# POWER.net
KiCad netlist of a schematic drawn in Altium Designer
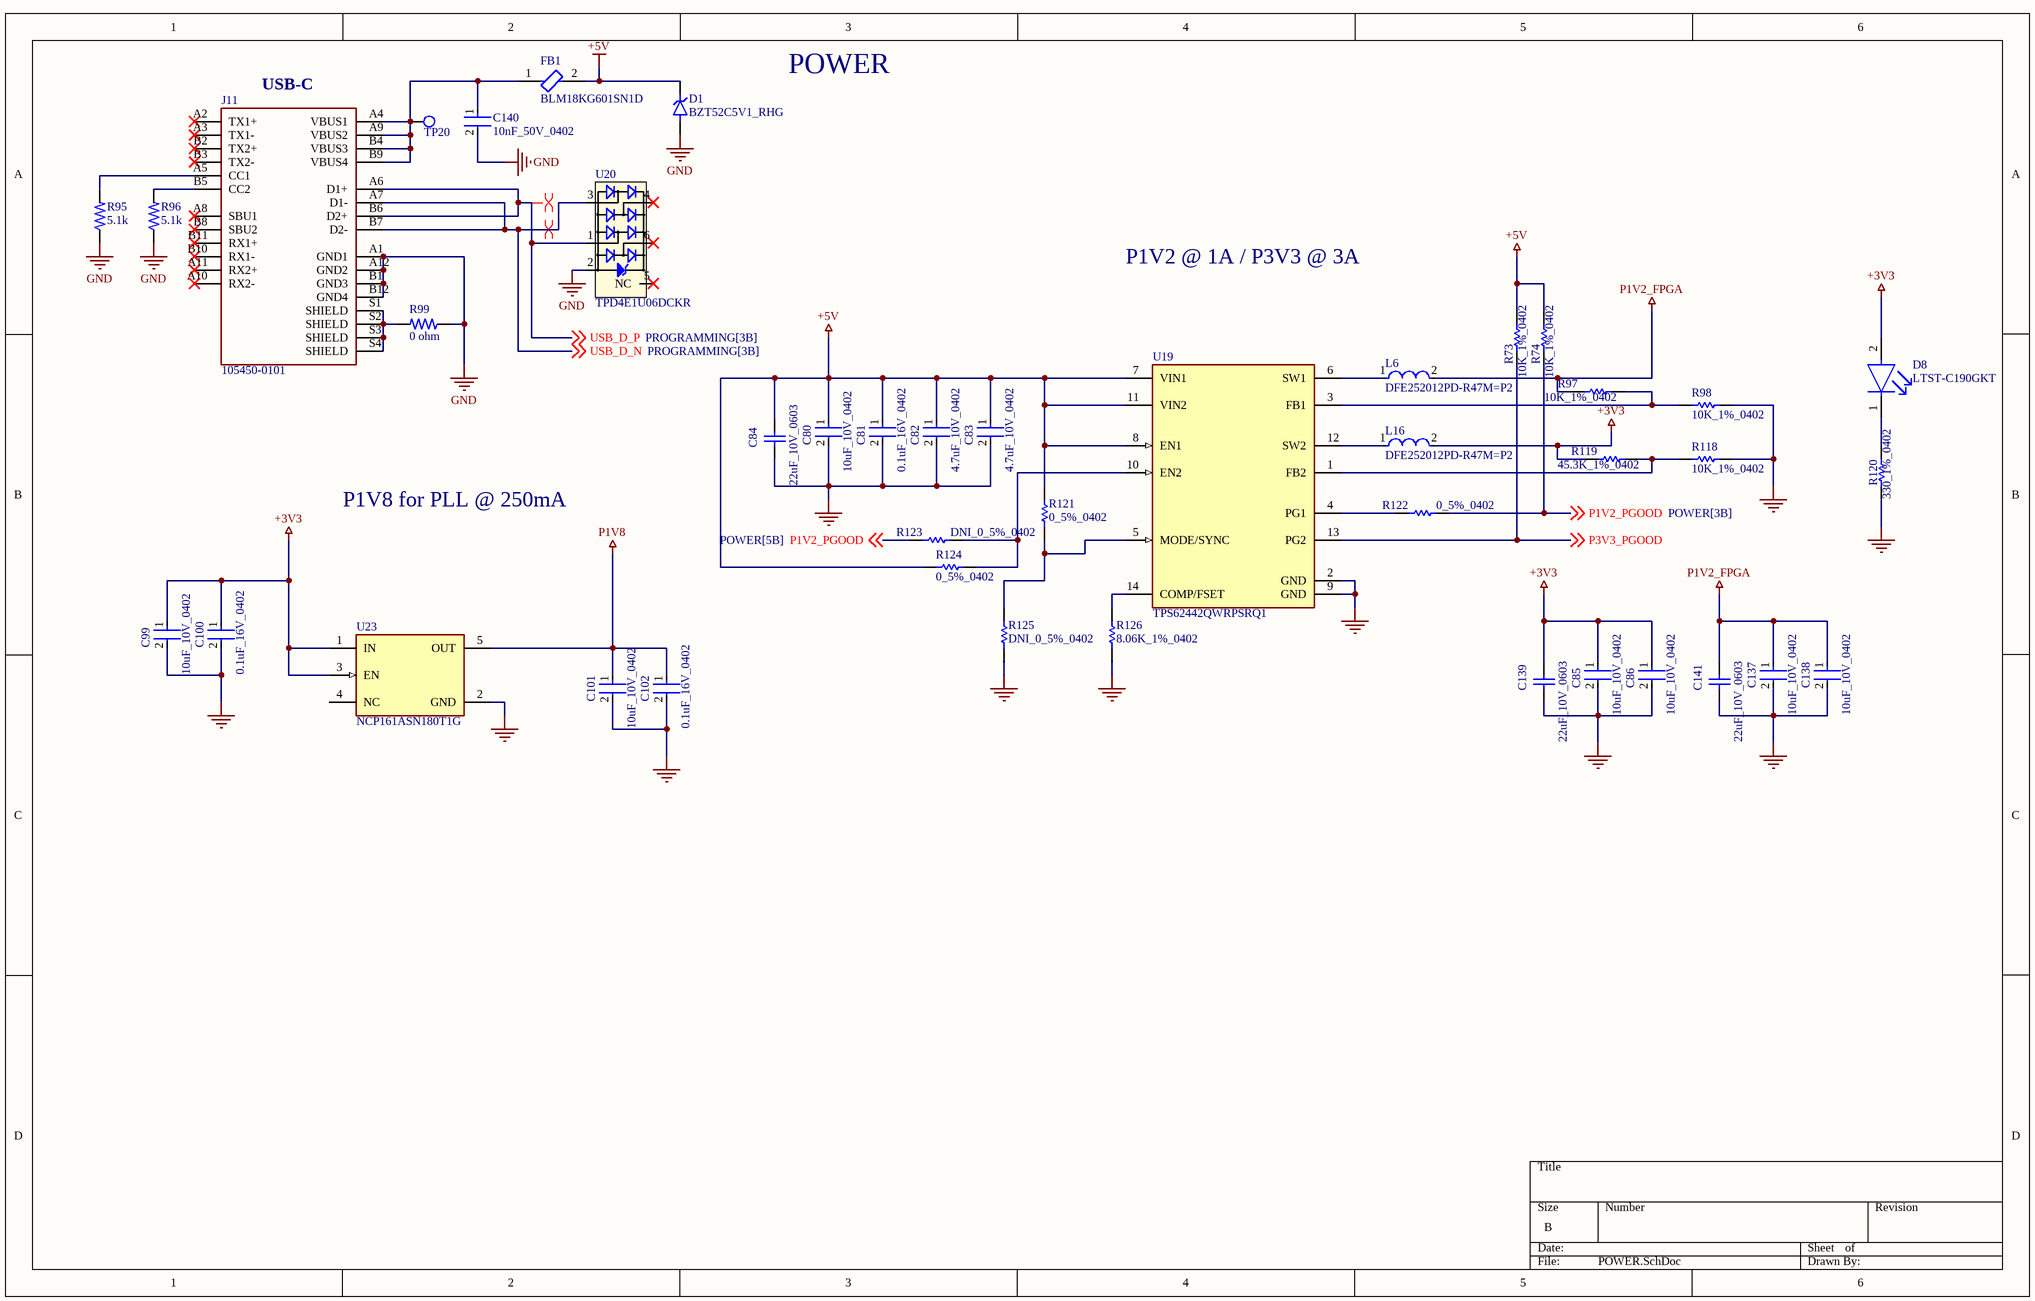
[diagram p0: POWER.SchDoc]

(export (version "E")
  (design (tool "Eeschema 10.0.6"))
  (components
    (comp (ref "C80")
      (value "10uF_10V_0402")
      (footprint "FP-CL05A106MP5NUNC-MFG")
      (description "CAP CER 10UF 10V X5R 0402")
      (fields
        (field (name "OCTOPART") "https://octopart.com/cl05a106mp5nunc-samsung-22457395")
        (field (name "TOLERANCE") "20%")
      )
      (libsource (lib "Altium Content Vault") (part "b4654b650e69147ec39a6b967a45e02"))
    )
    (comp (ref "C81")
      (value "0.1uF_16V_0402")
      (footprint "FP-C0402-BB-MFG")
      (description "CAP CER 0.1UF 16V 5% X7R 0402")
      (fields
        (field (name "MANUFACTURER") "Kemet")
        (field (name "MANUFACTURER PART NUMBER") "C0402C104J4RACTU")
      )
      (libsource (lib "Altium Content Vault") (part "b4654b650e69147ec39a6b967a45e02"))
    )
    (comp (ref "C82")
      (value "4.7uF_10V_0402")
      (footprint "FP-C1005-050-0_15-MFG")
      (description "CAP CER 4.7UF 10V X5R 0402")
      (fields (field (name "TOLERANCE") "10%"))
      (libsource (lib "Altium Content Vault") (part "b4654b650e69147ec39a6b967a45e02"))
    )
    (comp (ref "C83")
      (value "4.7uF_10V_0402")
      (footprint "FP-C1005-050-0_15-MFG")
      (description "CAP CER 4.7UF 10V X5R 0402")
      (fields (field (name "TOLERANCE") "10%"))
      (libsource (lib "Altium Content Vault") (part "b4654b650e69147ec39a6b967a45e02"))
    )
    (comp (ref "C84")
      (value "22uF_10V_0603")
      (footprint "CAPC1608X100X20ML10")
      (description "Chip Capacitor, 22 uF, +/- 20%, 10 V, -55 to 85 degC, 0603 (1608 Metric), RoHS, Tape and Reel")
      (fields (field (name "MANUFACTURER") "TDK") (field (name "TOLERANCE") "±20%"))
      (libsource (lib "Altium Content Vault") (part "CAP-NP-2"))
    )
    (comp (ref "C85")
      (value "10uF_10V_0402")
      (footprint "FP-CL05A106MP5NUNC-MFG")
      (description "CAP CER 10UF 10V X5R 0402")
      (fields
        (field (name "OCTOPART") "https://octopart.com/cl05a106mp5nunc-samsung-22457395")
        (field (name "TOLERANCE") "20%")
      )
      (libsource (lib "Altium Content Vault") (part "b4654b650e69147ec39a6b967a45e02"))
    )
    (comp (ref "C86")
      (value "10uF_10V_0402")
      (footprint "FP-CL05A106MP5NUNC-MFG")
      (description "CAP CER 10UF 10V X5R 0402")
      (fields
        (field (name "OCTOPART") "https://octopart.com/cl05a106mp5nunc-samsung-22457395")
        (field (name "TOLERANCE") "20%")
      )
      (libsource (lib "Altium Content Vault") (part "b4654b650e69147ec39a6b967a45e02"))
    )
    (comp (ref "C99")
      (value "10uF_10V_0402")
      (footprint "FP-CL05A106MP5NUNC-MFG")
      (description "CAP CER 10UF 10V X5R 0402")
      (fields
        (field (name "OCTOPART") "https://octopart.com/cl05a106mp5nunc-samsung-22457395")
        (field (name "TOLERANCE") "20%")
      )
      (libsource (lib "Altium Content Vault") (part "b4654b650e69147ec39a6b967a45e02"))
    )
    (comp (ref "C100")
      (value "0.1uF_16V_0402")
      (footprint "FP-C0402-BB-MFG")
      (description "CAP CER 0.1UF 16V 5% X7R 0402")
      (fields
        (field (name "MANUFACTURER") "Kemet")
        (field (name "MANUFACTURER PART NUMBER") "C0402C104J4RACTU")
      )
      (libsource (lib "Altium Content Vault") (part "b4654b650e69147ec39a6b967a45e02"))
    )
    (comp (ref "C101")
      (value "10uF_10V_0402")
      (footprint "FP-CL05A106MP5NUNC-MFG")
      (description "CAP CER 10UF 10V X5R 0402")
      (fields
        (field (name "OCTOPART") "https://octopart.com/cl05a106mp5nunc-samsung-22457395")
        (field (name "TOLERANCE") "20%")
      )
      (libsource (lib "Altium Content Vault") (part "b4654b650e69147ec39a6b967a45e02"))
    )
    (comp (ref "C102")
      (value "0.1uF_16V_0402")
      (footprint "FP-C0402-BB-MFG")
      (description "CAP CER 0.1UF 16V 5% X7R 0402")
      (fields
        (field (name "MANUFACTURER") "Kemet")
        (field (name "MANUFACTURER PART NUMBER") "C0402C104J4RACTU")
      )
      (libsource (lib "Altium Content Vault") (part "b4654b650e69147ec39a6b967a45e02"))
    )
    (comp (ref "C137")
      (value "10uF_10V_0402")
      (footprint "FP-CL05A106MP5NUNC-MFG")
      (description "CAP CER 10UF 10V X5R 0402")
      (fields
        (field (name "OCTOPART") "https://octopart.com/cl05a106mp5nunc-samsung-22457395")
        (field (name "TOLERANCE") "20%")
      )
      (libsource (lib "Altium Content Vault") (part "b4654b650e69147ec39a6b967a45e02"))
    )
    (comp (ref "C138")
      (value "10uF_10V_0402")
      (footprint "FP-CL05A106MP5NUNC-MFG")
      (description "CAP CER 10UF 10V X5R 0402")
      (fields
        (field (name "OCTOPART") "https://octopart.com/cl05a106mp5nunc-samsung-22457395")
        (field (name "TOLERANCE") "20%")
      )
      (libsource (lib "Altium Content Vault") (part "b4654b650e69147ec39a6b967a45e02"))
    )
    (comp (ref "C139")
      (value "22uF_10V_0603")
      (footprint "CAPC1608X100X20ML10")
      (description "Chip Capacitor, 22 uF, +/- 20%, 10 V, -55 to 85 degC, 0603 (1608 Metric), RoHS, Tape and Reel")
      (fields (field (name "MANUFACTURER") "TDK") (field (name "TOLERANCE") "±20%"))
      (libsource (lib "Altium Content Vault") (part "CAP-NP-2"))
    )
    (comp (ref "C140")
      (value "10nF_50V_0402")
      (footprint "FP-CL165-IPC_C")
      (description "Cap Ceramic 10nF 50V X7R ±10% SMD 0402 +125°C Paper T/R")
      (fields (field (name "VOLTAGE") "50V") (field (name "TOLERANCE") "10%"))
      (libsource (lib "Altium Content Vault") (part "b4654b650e69147ec39a6b967a45e02"))
    )
    (comp (ref "C141")
      (value "22uF_10V_0603")
      (footprint "CAPC1608X100X20ML10")
      (description "Chip Capacitor, 22 uF, +/- 20%, 10 V, -55 to 85 degC, 0603 (1608 Metric), RoHS, Tape and Reel")
      (fields (field (name "MANUFACTURER") "TDK") (field (name "TOLERANCE") "±20%"))
      (libsource (lib "Altium Content Vault") (part "CAP-NP-2"))
    )
    (comp (ref "D1")
      (value "BZT52C5V1_RHG")
      (footprint "D_BZT52C5V1_RHG")
      (description "Vz=5.1V 4.8V~5.4V Izt=5mA")
      (fields (field (name "MP") "BZT52C5V1 RHG") (field (name "MF") "Taiwan Semiconductor"))
      (libsource (lib "LotusSound") (part "D_BZT52C5V1_RHG"))
    )
    (comp (ref "D8")
      (value "LTST-C190GKT")
      (footprint "FP-LTST-C190GKT-MFG")
      (description "LED GREEN CLEAR CHIP SMD")
      (fields (field (name "VOLTAGE") "2V"))
      (libsource (lib "Altium Content Vault") (part "8706943c75ba83719d021d2fdc84c58"))
    )
    (comp (ref "FB1")
      (value "BLM18KG601SN1D")
      (footprint "FP-BLM18-0_15-t0_8-IPC_A")
      (description "Chip Ferrite Bead, 0603, 600Ω @ 100MHz, 0.15Ω, 25%, 1.3A")
      (fields (field (name "TOLERANCE") "25%"))
      (libsource (lib "Altium Content Vault") (part "5f30dd21d616792df468990f7003faa"))
    )
    (comp (ref "J11")
      (value "105450-0101")
      (footprint "CONN_105450-0101")
      (fields (field (name "MF") "Molex"))
      (libsource (lib "LotusSound") (part "CONN_105450-0101"))
    )
    (comp (ref "L6")
      (value "DFE252012PD-R47M=P2")
      (footprint "FP-DFE252012C-IPC_A")
      (description "Shielded Wirewound Inductor 0.47uH 20% 4000mA 0.027Ω 1008 (2520)")
      (libsource (lib "Altium Content Vault") (part "725321dda6339637d4d059423bc1c3c"))
    )
    (comp (ref "L16")
      (value "DFE252012PD-R47M=P2")
      (footprint "FP-DFE252012C-IPC_A")
      (description "Shielded Wirewound Inductor 0.47uH 20% 4000mA 0.027Ω 1008 (2520)")
      (libsource (lib "Altium Content Vault") (part "725321dda6339637d4d059423bc1c3c"))
    )
    (comp (ref "R73")
      (value "10K_1%_0402")
      (footprint "RESC1005X40X25NL10T10")
      (fields (field (name "MANUFACTURER") "Bourns") (field (name "PART NUMBER") "CR0402-FX-1002GLF"))
      (libsource (lib "Altium Content Vault") (part "RES"))
    )
    (comp (ref "R74")
      (value "10K_1%_0402")
      (footprint "RESC1005X40X25NL10T10")
      (fields (field (name "MANUFACTURER") "Bourns") (field (name "PART NUMBER") "CR0402-FX-1002GLF"))
      (libsource (lib "Altium Content Vault") (part "RES"))
    )
    (comp (ref "R95")
      (value "5.1k")
      (footprint "RES_0402")
      (description "Res Thick Film 0402 5.1K Ohm 1% 0.063W ±100ppm/°C Molded SMD Paper T/R")
      (fields
        (field (name "MANUFACTURER") "Stackpole Electronics")
        (field (name "MANUFACTURER PART NUMBER") "RMCF0402FT5K10")
      )
      (libsource (lib "LotusSound") (part "RES_RMCF0402FT5K10"))
    )
    (comp (ref "R96")
      (value "5.1k")
      (footprint "RES_0402")
      (description "Res Thick Film 0402 5.1K Ohm 1% 0.063W ±100ppm/°C Molded SMD Paper T/R")
      (fields
        (field (name "MANUFACTURER") "Stackpole Electronics")
        (field (name "MANUFACTURER PART NUMBER") "RMCF0402FT5K10")
      )
      (libsource (lib "LotusSound") (part "RES_RMCF0402FT5K10"))
    )
    (comp (ref "R97")
      (value "10K_1%_0402")
      (footprint "RESC1005X40X25NL10T10")
      (fields (field (name "MANUFACTURER") "Bourns") (field (name "PART NUMBER") "CR0402-FX-1002GLF"))
      (libsource (lib "Altium Content Vault") (part "RES"))
    )
    (comp (ref "R98")
      (value "10K_1%_0402")
      (footprint "RESC1005X40X25NL10T10")
      (fields (field (name "MANUFACTURER") "Bourns") (field (name "PART NUMBER") "CR0402-FX-1002GLF"))
      (libsource (lib "Altium Content Vault") (part "RES"))
    )
    (comp (ref "R99")
      (value "0 ohm")
      (footprint "RES_0402")
      (description "RES SMD 0 OHM JUMPER 1/16W 0402")
      (fields
        (field (name "MANUFACTURER") "Yageo")
        (field (name "MANUFACTURER PART NUMBER") "RC0402JR-070RL")
      )
      (libsource (lib "LotusSound") (part "RES_RC0402JR-070RL"))
    )
    (comp (ref "R118")
      (value "10K_1%_0402")
      (footprint "RESC1005X40X25NL10T10")
      (fields (field (name "MANUFACTURER") "Bourns") (field (name "PART NUMBER") "CR0402-FX-1002GLF"))
      (libsource (lib "Altium Content Vault") (part "RES"))
    )
    (comp (ref "R119")
      (value "45.3K_1%_0402")
      (footprint "RESC0402(1005)_L")
      (description "45K3 0.063W 1% 0402 (1005 Metric)  SMD")
      (fields (field (name "TOLERANCE") "1 %") (field (name "POWER") "0.063 W"))
      (libsource (lib "Altium Content Vault") (part "RES"))
    )
    (comp (ref "R120")
      (value "330_1%_0402")
      (footprint "RESC1005X40X25NL10T10")
      (fields (field (name "MANUFACTURER") "Panasonic") (field (name "PART NUMBER") "ERA-2AED331X"))
      (libsource (lib "Altium Content Vault") (part "RES"))
    )
    (comp (ref "R121")
      (value "0_5%_0402")
      (footprint "RESC1005X40X25NL05T10")
      (fields (field (name "MANUFACTURER") "Panasonic") (field (name "PART NUMBER") "ERJ-U020R00X"))
      (libsource (lib "Altium Content Vault") (part "RES"))
    )
    (comp (ref "R122")
      (value "0_5%_0402")
      (footprint "RESC1005X40X25NL05T10")
      (fields (field (name "MANUFACTURER") "Panasonic") (field (name "PART NUMBER") "ERJ-U020R00X"))
      (libsource (lib "Altium Content Vault") (part "RES"))
    )
    (comp (ref "R123")
      (value "DNI_0_5%_0402")
      (footprint "RESC1005X40X25NL05T10")
      (fields (field (name "MANUFACTURER") "Panasonic") (field (name "PART NUMBER") "ERJ-U020R00X"))
      (libsource (lib "Altium Content Vault") (part "RES"))
    )
    (comp (ref "R124")
      (value "0_5%_0402")
      (footprint "RESC1005X40X25NL05T10")
      (fields (field (name "MANUFACTURER") "Panasonic") (field (name "PART NUMBER") "ERJ-U020R00X"))
      (libsource (lib "Altium Content Vault") (part "RES"))
    )
    (comp (ref "R125")
      (value "DNI_0_5%_0402")
      (footprint "RESC1005X40X25NL05T10")
      (fields (field (name "MANUFACTURER") "Panasonic") (field (name "PART NUMBER") "ERJ-U020R00X"))
      (libsource (lib "Altium Content Vault") (part "RES"))
    )
    (comp (ref "R126")
      (value "8.06K_1%_0402")
      (footprint "RESC1005X40X25ML05T05")
      (description "Chip Resistor, 8.06 KOhm, +/- 1%, 63 mW, -55 to 155 degC, 0402 (1005 Metric), RoHS, Tape and Reel")
      (fields (field (name "PARTNUMBER") "CRCW04028K06FKED") (field (name "TOLERANCE") "1%"))
      (libsource (lib "Altium Content Vault") (part "RES-2"))
    )
    (comp (ref "TP20")
      (value "Test Point 1MM")
      (footprint "TP_PAD-1MM")
      (libsource (lib "LotusSound") (part "TP_PAD-1MM"))
    )
    (comp (ref "U19")
      (value "TPS62442QWRPSRQ1")
      (footprint "FP-RQR0014A-MFG")
      (description "Adjustable-Frequency Dual Step-Down Converter, 2.7-6V VIN, 0.6-5.5V 2A VOUT, VQFN-HR14")
      (libsource (lib "Altium Content Vault") (part "72c5b9bb22caeb688b1070b758806aa"))
    )
    (comp (ref "U20")
      (value "TPD4E1U06DCKR")
      (footprint "IC_TPD4E1U06DCKR")
      (description "TVS DIODE 5.5VWM 15VC SC70-6")
      (fields (field (name "MANUFACTURER") "Texas Instruments"))
      (libsource (lib "LotusSound") (part "IC_TPD4E1U06DCKR"))
    )
    (comp (ref "U23")
      (value "NCP161ASN180T1G")
      (footprint "FP-527AH-MFG")
      (libsource (lib "Altium Content Vault") (part "07e51adf658dd7550fcbd1980b41b01"))
    )
  )
  (nets
    (net (code "1") (name "+3V3") (class "Default")
      (node (ref "C100") (pin "1") (pinfunction "1_1") (pintype "passive"))
      (node (ref "C139") (pin "2") (pinfunction "2_2") (pintype "passive"))
      (node (ref "C85") (pin "1") (pinfunction "1_1") (pintype "passive"))
      (node (ref "C86") (pin "1") (pinfunction "1_1") (pintype "passive"))
      (node (ref "C99") (pin "1") (pinfunction "1_1") (pintype "passive"))
      (node (ref "D8") (pin "2") (pinfunction "A_2") (pintype "passive"))
      (node (ref "L16") (pin "2") (pinfunction "2_2") (pintype "passive"))
      (node (ref "R119") (pin "1") (pinfunction "1_1") (pintype "passive"))
      (node (ref "U23") (pin "1") (pinfunction "IN_1") (pintype "power_in"))
      (node (ref "U23") (pin "3") (pinfunction "EN_3") (pintype "input"))
    )
    (net (code "2") (name "+5V") (class "Default")
      (node (ref "C80") (pin "1") (pinfunction "1_1") (pintype "passive"))
      (node (ref "C81") (pin "1") (pinfunction "1_1") (pintype "passive"))
      (node (ref "C82") (pin "1") (pinfunction "1_1") (pintype "passive"))
      (node (ref "C83") (pin "1") (pinfunction "1_1") (pintype "passive"))
      (node (ref "C84") (pin "2") (pinfunction "2_2") (pintype "passive"))
      (node (ref "D1") (pin "C") (pinfunction "K_C") (pintype "passive"))
      (node (ref "FB1") (pin "2") (pinfunction "2_2") (pintype "passive"))
      (node (ref "R121") (pin "2") (pinfunction "2_2") (pintype "passive"))
      (node (ref "R124") (pin "2") (pinfunction "2_2") (pintype "passive"))
      (node (ref "R73") (pin "2") (pinfunction "2_2") (pintype "passive"))
      (node (ref "R74") (pin "2") (pinfunction "2_2") (pintype "passive"))
      (node (ref "U19") (pin "11") (pinfunction "VIN2_11") (pintype "power_in"))
      (node (ref "U19") (pin "7") (pinfunction "VIN1_7") (pintype "power_in"))
      (node (ref "U19") (pin "8") (pinfunction "EN1_8") (pintype "input"))
    )
    (net (code "3") (name "GND") (class "Default")
      (node (ref "C100") (pin "2") (pinfunction "2_2") (pintype "passive"))
      (node (ref "C101") (pin "2") (pinfunction "2_2") (pintype "passive"))
      (node (ref "C102") (pin "2") (pinfunction "2_2") (pintype "passive"))
      (node (ref "C137") (pin "2") (pinfunction "2_2") (pintype "passive"))
      (node (ref "C138") (pin "2") (pinfunction "2_2") (pintype "passive"))
      (node (ref "C139") (pin "1") (pinfunction "1_1") (pintype "passive"))
      (node (ref "C140") (pin "2") (pinfunction "2_2") (pintype "passive"))
      (node (ref "C141") (pin "1") (pinfunction "1_1") (pintype "passive"))
      (node (ref "C80") (pin "2") (pinfunction "2_2") (pintype "passive"))
      (node (ref "C81") (pin "2") (pinfunction "2_2") (pintype "passive"))
      (node (ref "C82") (pin "2") (pinfunction "2_2") (pintype "passive"))
      (node (ref "C83") (pin "2") (pinfunction "2_2") (pintype "passive"))
      (node (ref "C84") (pin "1") (pinfunction "1_1") (pintype "passive"))
      (node (ref "C85") (pin "2") (pinfunction "2_2") (pintype "passive"))
      (node (ref "C86") (pin "2") (pinfunction "2_2") (pintype "passive"))
      (node (ref "C99") (pin "2") (pinfunction "2_2") (pintype "passive"))
      (node (ref "D1") (pin "A") (pinfunction "A_A") (pintype "passive"))
      (node (ref "J11") (pin "A1") (pinfunction "GND1_A1") (pintype "passive"))
      (node (ref "J11") (pin "A12") (pinfunction "GND2_A12") (pintype "passive"))
      (node (ref "J11") (pin "B1") (pinfunction "GND3_B1") (pintype "passive"))
      (node (ref "J11") (pin "B12") (pinfunction "GND4_B12") (pintype "passive"))
      (node (ref "R118") (pin "1") (pinfunction "1_1") (pintype "passive"))
      (node (ref "R120") (pin "1") (pinfunction "1_1") (pintype "passive"))
      (node (ref "R125") (pin "1") (pinfunction "1_1") (pintype "passive"))
      (node (ref "R126") (pin "1") (pinfunction "1_1") (pintype "passive"))
      (node (ref "R95") (pin "1") (pinfunction "1_1") (pintype "passive"))
      (node (ref "R96") (pin "1") (pinfunction "1_1") (pintype "passive"))
      (node (ref "R98") (pin "1") (pinfunction "1_1") (pintype "passive"))
      (node (ref "R99") (pin "1") (pinfunction "1_1") (pintype "passive"))
      (node (ref "U19") (pin "2") (pinfunction "GND_2") (pintype "power_in"))
      (node (ref "U19") (pin "9") (pinfunction "GND_9") (pintype "power_in"))
      (node (ref "U20") (pin "2") (pinfunction "GND_2") (pintype "passive"))
      (node (ref "U23") (pin "2") (pinfunction "GND_2") (pintype "power_in"))
    )
    (net (code "4") (name "Net-(D8-C)") (class "Default")
      (node (ref "D8") (pin "1") (pinfunction "C_1") (pintype "passive"))
      (node (ref "R120") (pin "2") (pinfunction "2_2") (pintype "passive"))
    )
    (net (code "5") (name "Net-(J11-CC1)") (class "Default")
      (node (ref "J11") (pin "A5") (pinfunction "CC1_A5") (pintype "passive"))
      (node (ref "R95") (pin "2") (pinfunction "2_2") (pintype "passive"))
    )
    (net (code "6") (name "Net-(J11-CC2)") (class "Default")
      (node (ref "J11") (pin "B5") (pinfunction "CC2_B5") (pintype "passive"))
      (node (ref "R96") (pin "2") (pinfunction "2_2") (pintype "passive"))
    )
    (net (code "7") (name "Net-(J11-SHIELD-PadS1)") (class "Default")
      (node (ref "J11") (pin "S1") (pinfunction "SHIELD_S1") (pintype "passive"))
      (node (ref "J11") (pin "S2") (pinfunction "SHIELD_S2") (pintype "passive"))
      (node (ref "J11") (pin "S3") (pinfunction "SHIELD_S3") (pintype "passive"))
      (node (ref "J11") (pin "S4") (pinfunction "SHIELD_S4") (pintype "passive"))
      (node (ref "R99") (pin "2") (pinfunction "2_2") (pintype "passive"))
    )
    (net (code "8") (name "Net-(J11-VBUS1)") (class "Default")
      (node (ref "C140") (pin "1") (pinfunction "1_1") (pintype "passive"))
      (node (ref "FB1") (pin "1") (pinfunction "1_1") (pintype "passive"))
      (node (ref "J11") (pin "A4") (pinfunction "VBUS1_A4") (pintype "passive"))
      (node (ref "J11") (pin "A9") (pinfunction "VBUS2_A9") (pintype "passive"))
      (node (ref "J11") (pin "B4") (pinfunction "VBUS3_B4") (pintype "passive"))
      (node (ref "J11") (pin "B9") (pinfunction "VBUS4_B9") (pintype "passive"))
      (node (ref "TP20") (pin "1") (pinfunction "1_1") (pintype "passive"))
    )
    (net (code "9") (name "Net-(U19-COMP{slash}FSET)") (class "Default")
      (node (ref "R126") (pin "2") (pinfunction "2_2") (pintype "passive"))
      (node (ref "U19") (pin "14") (pinfunction "COMP/FSET_14") (pintype "passive"))
    )
    (net (code "10") (name "Net-(U19-EN2)") (class "Default")
      (node (ref "R123") (pin "2") (pinfunction "2_2") (pintype "passive"))
      (node (ref "R124") (pin "1") (pinfunction "1_1") (pintype "passive"))
      (node (ref "U19") (pin "10") (pinfunction "EN2_10") (pintype "input"))
    )
    (net (code "11") (name "Net-(U19-FB1)") (class "Default")
      (node (ref "R97") (pin "1") (pinfunction "1_1") (pintype "passive"))
      (node (ref "R98") (pin "2") (pinfunction "2_2") (pintype "passive"))
      (node (ref "U19") (pin "3") (pinfunction "FB1_3") (pintype "passive"))
    )
    (net (code "12") (name "Net-(U19-FB2)") (class "Default")
      (node (ref "R118") (pin "2") (pinfunction "2_2") (pintype "passive"))
      (node (ref "R119") (pin "2") (pinfunction "2_2") (pintype "passive"))
      (node (ref "U19") (pin "1") (pinfunction "FB2_1") (pintype "passive"))
    )
    (net (code "13") (name "Net-(U19-MODE{slash}SYNC)") (class "Default")
      (node (ref "R121") (pin "1") (pinfunction "1_1") (pintype "passive"))
      (node (ref "R125") (pin "2") (pinfunction "2_2") (pintype "passive"))
      (node (ref "U19") (pin "5") (pinfunction "MODE/SYNC_5") (pintype "input"))
    )
    (net (code "14") (name "Net-(U19-PG1)") (class "Default")
      (node (ref "R122") (pin "1") (pinfunction "1_1") (pintype "passive"))
      (node (ref "U19") (pin "4") (pinfunction "PG1_4") (pintype "open_collector"))
    )
    (net (code "15") (name "Net-(U19-SW1)") (class "Default")
      (node (ref "L6") (pin "1") (pinfunction "1_1") (pintype "passive"))
      (node (ref "U19") (pin "6") (pinfunction "SW1_6") (pintype "passive"))
    )
    (net (code "16") (name "Net-(U19-SW2)") (class "Default")
      (node (ref "L16") (pin "1") (pinfunction "1_1") (pintype "passive"))
      (node (ref "U19") (pin "12") (pinfunction "SW2_12") (pintype "passive"))
    )
    (net (code "17") (name "P1V2_FPGA") (class "Default")
      (node (ref "C137") (pin "1") (pinfunction "1_1") (pintype "passive"))
      (node (ref "C138") (pin "1") (pinfunction "1_1") (pintype "passive"))
      (node (ref "C141") (pin "2") (pinfunction "2_2") (pintype "passive"))
      (node (ref "L6") (pin "2") (pinfunction "2_2") (pintype "passive"))
      (node (ref "R97") (pin "2") (pinfunction "2_2") (pintype "passive"))
    )
    (net (code "18") (name "P1V2_PGOOD") (class "Default")
      (node (ref "R122") (pin "2") (pinfunction "2_2") (pintype "passive"))
      (node (ref "R123") (pin "1") (pinfunction "1_1") (pintype "passive"))
      (node (ref "R74") (pin "1") (pinfunction "1_1") (pintype "passive"))
    )
    (net (code "19") (name "P1V8") (class "Default")
      (node (ref "C101") (pin "1") (pinfunction "1_1") (pintype "passive"))
      (node (ref "C102") (pin "1") (pinfunction "1_1") (pintype "passive"))
      (node (ref "U23") (pin "5") (pinfunction "OUT_5") (pintype "passive"))
    )
    (net (code "20") (name "P3V3_PGOOD") (class "Default")
      (node (ref "R73") (pin "1") (pinfunction "1_1") (pintype "passive"))
      (node (ref "U19") (pin "13") (pinfunction "PG2_13") (pintype "open_collector"))
    )
    (net (code "21") (name "USB_D_N") (class "Default")
      (node (ref "J11") (pin "A7") (pinfunction "D1-_A7") (pintype "passive"))
      (node (ref "J11") (pin "B7") (pinfunction "D2-_B7") (pintype "passive"))
      (node (ref "U20") (pin "3") (pinfunction "D+_3") (pintype "passive"))
    )
    (net (code "22") (name "USB_D_P") (class "Default")
      (node (ref "J11") (pin "A6") (pinfunction "D1+_A6") (pintype "passive"))
      (node (ref "J11") (pin "B6") (pinfunction "D2+_B6") (pintype "passive"))
      (node (ref "U20") (pin "1") (pinfunction "D+_1") (pintype "passive"))
    )
    (net (code "23") (name "unconnected-(J11-RX1+-PadB11)") (class "Default")
      (node (ref "J11") (pin "B11") (pinfunction "RX1+_B11") (pintype "passive+no_connect"))
    )
    (net (code "24") (name "unconnected-(J11-RX1--PadB10)") (class "Default")
      (node (ref "J11") (pin "B10") (pinfunction "RX1-_B10") (pintype "passive+no_connect"))
    )
    (net (code "25") (name "unconnected-(J11-RX2+-PadA11)") (class "Default")
      (node (ref "J11") (pin "A11") (pinfunction "RX2+_A11") (pintype "passive+no_connect"))
    )
    (net (code "26") (name "unconnected-(J11-RX2--PadA10)") (class "Default")
      (node (ref "J11") (pin "A10") (pinfunction "RX2-_A10") (pintype "passive+no_connect"))
    )
    (net (code "27") (name "unconnected-(J11-SBU1-PadA8)") (class "Default")
      (node (ref "J11") (pin "A8") (pinfunction "SBU1_A8") (pintype "passive+no_connect"))
    )
    (net (code "28") (name "unconnected-(J11-SBU2-PadB8)") (class "Default")
      (node (ref "J11") (pin "B8") (pinfunction "SBU2_B8") (pintype "passive+no_connect"))
    )
    (net (code "29") (name "unconnected-(J11-TX1+-PadA2)") (class "Default")
      (node (ref "J11") (pin "A2") (pinfunction "TX1+_A2") (pintype "passive+no_connect"))
    )
    (net (code "30") (name "unconnected-(J11-TX1--PadA3)") (class "Default")
      (node (ref "J11") (pin "A3") (pinfunction "TX1-_A3") (pintype "passive+no_connect"))
    )
    (net (code "31") (name "unconnected-(J11-TX2+-PadB2)") (class "Default")
      (node (ref "J11") (pin "B2") (pinfunction "TX2+_B2") (pintype "passive+no_connect"))
    )
    (net (code "32") (name "unconnected-(J11-TX2--PadB3)") (class "Default")
      (node (ref "J11") (pin "B3") (pinfunction "TX2-_B3") (pintype "passive+no_connect"))
    )
    (net (code "33") (name "unconnected-(U20-D--Pad4)") (class "Default")
      (node (ref "U20") (pin "4") (pinfunction "D-_4") (pintype "passive+no_connect"))
    )
    (net (code "34") (name "unconnected-(U20-D--Pad6)") (class "Default")
      (node (ref "U20") (pin "6") (pinfunction "D-_6") (pintype "passive+no_connect"))
    )
    (net (code "35") (name "unconnected-(U20-NC-Pad5)") (class "Default")
      (node (ref "U20") (pin "5") (pinfunction "NC_5") (pintype "passive+no_connect"))
    )
    (net (code "36") (name "unconnected-(U23-NC-Pad4)") (class "Default")
      (node (ref "U23") (pin "4") (pinfunction "NC_4") (pintype "passive"))
    )
  )
)
